# ShieldUart.net
KiCad netlist of a schematic drawn in Altium Designer
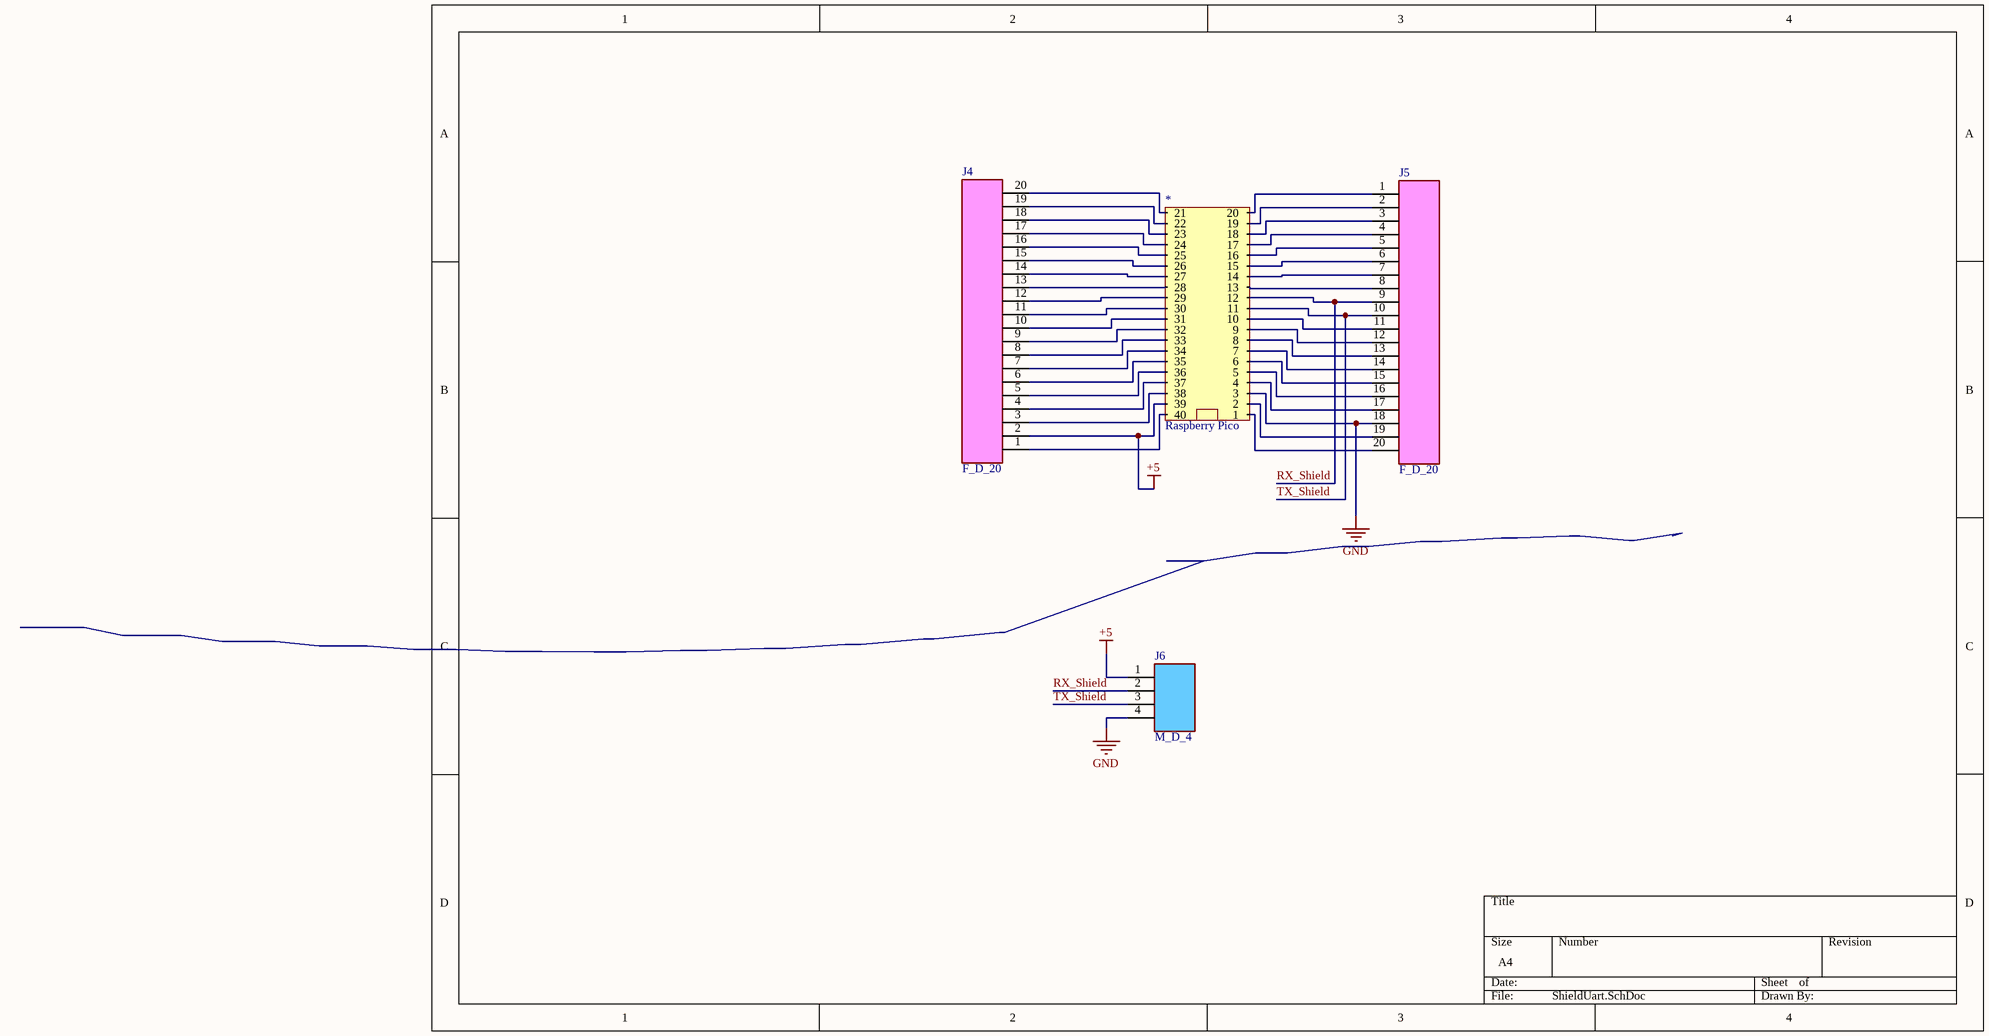
[diagram p0: ShieldUart.SchDoc]

(export (version "E")
  (design (tool "Eeschema 10.0.6"))
  (components
    (comp (ref "*")
      (value "Raspberry Pico")
      (footprint "Raspberry Pico")
      (libsource (lib "MyComponent") (part "Raspberry Pico"))
    )
    (comp (ref "J4")
      (value "BARRETTE_20 CONTACTS_1 RANGEE_FEMELLE_DROITE")
      (footprint "BARRETTE_20_F_D")
      (fields (field (name "TYPE") "F_D_20"))
      (libsource (lib "connecteurs") (part "BARRETTE_20 CONTACTS_1 RANGEE_FEMELLE_DROITE"))
    )
    (comp (ref "J5")
      (value "BARRETTE_20 CONTACTS_1 RANGEE_FEMELLE_DROITE")
      (footprint "BARRETTE_20_F_D")
      (fields (field (name "TYPE") "F_D_20"))
      (libsource (lib "") (part "BARRETTE_20 CONTACTS_1 RANGEE_FEMELLE_DROITE_1"))
    )
    (comp (ref "J6")
      (value "BARRETTE_4 CONTACTS_1 RANGEE_MALE_DROITE")
      (footprint "BARRETTE_4_M_D")
      (description "BARRETTE 4 CONTACTS 1 RANGEE MALE DROITE")
      (fields (field (name "TYPE") "M_D_4"))
      (libsource (lib "connecteurs") (part "BARRETTE_4 CONTACTS_1 RANGEE_MALE_DROITE"))
    )
  )
  (nets
    (net (code "1") (name "+5") (class "Default")
      (node (ref "*") (pin "39") (pinfunction "39_39") (pintype "passive"))
      (node (ref "J4") (pin "2") (pinfunction "2_2") (pintype "passive"))
      (node (ref "J6") (pin "1") (pinfunction "1_1") (pintype "passive"))
    )
    (net (code "2") (name "/RX_Shield") (class "Default")
      (node (ref "*") (pin "12") (pinfunction "12_12") (pintype "passive"))
      (node (ref "J5") (pin "9") (pinfunction "9_9") (pintype "passive"))
      (node (ref "J6") (pin "2") (pinfunction "2_2") (pintype "passive"))
    )
    (net (code "3") (name "/TX_Shield") (class "Default")
      (node (ref "*") (pin "11") (pinfunction "11_11") (pintype "passive"))
      (node (ref "J5") (pin "10") (pinfunction "10_10") (pintype "passive"))
      (node (ref "J6") (pin "3") (pinfunction "3_3") (pintype "passive"))
    )
    (net (code "4") (name "GND") (class "Default")
      (node (ref "*") (pin "3") (pinfunction "3_3") (pintype "passive"))
      (node (ref "J5") (pin "18") (pinfunction "18_18") (pintype "passive"))
      (node (ref "J6") (pin "4") (pinfunction "4_4") (pintype "passive"))
    )
    (net (code "5") (name "Net-(*-Pad1)") (class "Default")
      (node (ref "*") (pin "1") (pinfunction "1_1") (pintype "passive"))
      (node (ref "J5") (pin "20") (pinfunction "20_20") (pintype "passive"))
    )
    (net (code "6") (name "Net-(*-Pad2)") (class "Default")
      (node (ref "*") (pin "2") (pinfunction "2_2") (pintype "passive"))
      (node (ref "J5") (pin "19") (pinfunction "19_19") (pintype "passive"))
    )
    (net (code "7") (name "Net-(*-Pad4)") (class "Default")
      (node (ref "*") (pin "4") (pinfunction "4_4") (pintype "passive"))
      (node (ref "J5") (pin "17") (pinfunction "17_17") (pintype "passive"))
    )
    (net (code "8") (name "Net-(*-Pad5)") (class "Default")
      (node (ref "*") (pin "5") (pinfunction "5_5") (pintype "passive"))
      (node (ref "J5") (pin "16") (pinfunction "16_16") (pintype "passive"))
    )
    (net (code "9") (name "Net-(*-Pad6)") (class "Default")
      (node (ref "*") (pin "6") (pinfunction "6_6") (pintype "passive"))
      (node (ref "J5") (pin "15") (pinfunction "15_15") (pintype "passive"))
    )
    (net (code "10") (name "Net-(*-Pad7)") (class "Default")
      (node (ref "*") (pin "7") (pinfunction "7_7") (pintype "passive"))
      (node (ref "J5") (pin "14") (pinfunction "14_14") (pintype "passive"))
    )
    (net (code "11") (name "Net-(*-Pad8)") (class "Default")
      (node (ref "*") (pin "8") (pinfunction "8_8") (pintype "passive"))
      (node (ref "J5") (pin "13") (pinfunction "13_13") (pintype "passive"))
    )
    (net (code "12") (name "Net-(*-Pad9)") (class "Default")
      (node (ref "*") (pin "9") (pinfunction "9_9") (pintype "passive"))
      (node (ref "J5") (pin "12") (pinfunction "12_12") (pintype "passive"))
    )
    (net (code "13") (name "Net-(*-Pad10)") (class "Default")
      (node (ref "*") (pin "10") (pinfunction "10_10") (pintype "passive"))
      (node (ref "J5") (pin "11") (pinfunction "11_11") (pintype "passive"))
    )
    (net (code "14") (name "Net-(*-Pad13)") (class "Default")
      (node (ref "*") (pin "13") (pinfunction "13_13") (pintype "passive"))
      (node (ref "J5") (pin "8") (pinfunction "8_8") (pintype "passive"))
    )
    (net (code "15") (name "Net-(*-Pad14)") (class "Default")
      (node (ref "*") (pin "14") (pinfunction "14_14") (pintype "passive"))
      (node (ref "J5") (pin "7") (pinfunction "7_7") (pintype "passive"))
    )
    (net (code "16") (name "Net-(*-Pad15)") (class "Default")
      (node (ref "*") (pin "15") (pinfunction "15_15") (pintype "passive"))
      (node (ref "J5") (pin "6") (pinfunction "6_6") (pintype "passive"))
    )
    (net (code "17") (name "Net-(*-Pad16)") (class "Default")
      (node (ref "*") (pin "16") (pinfunction "16_16") (pintype "passive"))
      (node (ref "J5") (pin "5") (pinfunction "5_5") (pintype "passive"))
    )
    (net (code "18") (name "Net-(*-Pad17)") (class "Default")
      (node (ref "*") (pin "17") (pinfunction "17_17") (pintype "passive"))
      (node (ref "J5") (pin "4") (pinfunction "4_4") (pintype "passive"))
    )
    (net (code "19") (name "Net-(*-Pad18)") (class "Default")
      (node (ref "*") (pin "18") (pinfunction "18_18") (pintype "passive"))
      (node (ref "J5") (pin "3") (pinfunction "3_3") (pintype "passive"))
    )
    (net (code "20") (name "Net-(*-Pad19)") (class "Default")
      (node (ref "*") (pin "19") (pinfunction "19_19") (pintype "passive"))
      (node (ref "J5") (pin "2") (pinfunction "2_2") (pintype "passive"))
    )
    (net (code "21") (name "Net-(*-Pad20)") (class "Default")
      (node (ref "*") (pin "20") (pinfunction "20_20") (pintype "passive"))
      (node (ref "J5") (pin "1") (pinfunction "1_1") (pintype "passive"))
    )
    (net (code "22") (name "Net-(*-Pad21)") (class "Default")
      (node (ref "*") (pin "21") (pinfunction "21_21") (pintype "passive"))
      (node (ref "J4") (pin "20") (pinfunction "20_20") (pintype "passive"))
    )
    (net (code "23") (name "Net-(*-Pad22)") (class "Default")
      (node (ref "*") (pin "22") (pinfunction "22_22") (pintype "passive"))
      (node (ref "J4") (pin "19") (pinfunction "19_19") (pintype "passive"))
    )
    (net (code "24") (name "Net-(*-Pad23)") (class "Default")
      (node (ref "*") (pin "23") (pinfunction "23_23") (pintype "passive"))
      (node (ref "J4") (pin "18") (pinfunction "18_18") (pintype "passive"))
    )
    (net (code "25") (name "Net-(*-Pad24)") (class "Default")
      (node (ref "*") (pin "24") (pinfunction "24_24") (pintype "passive"))
      (node (ref "J4") (pin "17") (pinfunction "17_17") (pintype "passive"))
    )
    (net (code "26") (name "Net-(*-Pad25)") (class "Default")
      (node (ref "*") (pin "25") (pinfunction "25_25") (pintype "passive"))
      (node (ref "J4") (pin "16") (pinfunction "16_16") (pintype "passive"))
    )
    (net (code "27") (name "Net-(*-Pad26)") (class "Default")
      (node (ref "*") (pin "26") (pinfunction "26_26") (pintype "passive"))
      (node (ref "J4") (pin "15") (pinfunction "15_15") (pintype "passive"))
    )
    (net (code "28") (name "Net-(*-Pad27)") (class "Default")
      (node (ref "*") (pin "27") (pinfunction "27_27") (pintype "passive"))
      (node (ref "J4") (pin "14") (pinfunction "14_14") (pintype "passive"))
    )
    (net (code "29") (name "Net-(*-Pad28)") (class "Default")
      (node (ref "*") (pin "28") (pinfunction "28_28") (pintype "passive"))
      (node (ref "J4") (pin "13") (pinfunction "13_13") (pintype "passive"))
    )
    (net (code "30") (name "Net-(*-Pad29)") (class "Default")
      (node (ref "*") (pin "29") (pinfunction "29_29") (pintype "passive"))
      (node (ref "J4") (pin "12") (pinfunction "12_12") (pintype "passive"))
    )
    (net (code "31") (name "Net-(*-Pad30)") (class "Default")
      (node (ref "*") (pin "30") (pinfunction "30_30") (pintype "passive"))
      (node (ref "J4") (pin "11") (pinfunction "11_11") (pintype "passive"))
    )
    (net (code "32") (name "Net-(*-Pad31)") (class "Default")
      (node (ref "*") (pin "31") (pinfunction "31_31") (pintype "passive"))
      (node (ref "J4") (pin "10") (pinfunction "10_10") (pintype "passive"))
    )
    (net (code "33") (name "Net-(*-Pad32)") (class "Default")
      (node (ref "*") (pin "32") (pinfunction "32_32") (pintype "passive"))
      (node (ref "J4") (pin "9") (pinfunction "9_9") (pintype "passive"))
    )
    (net (code "34") (name "Net-(*-Pad33)") (class "Default")
      (node (ref "*") (pin "33") (pinfunction "33_33") (pintype "passive"))
      (node (ref "J4") (pin "8") (pinfunction "8_8") (pintype "passive"))
    )
    (net (code "35") (name "Net-(*-Pad34)") (class "Default")
      (node (ref "*") (pin "34") (pinfunction "34_34") (pintype "passive"))
      (node (ref "J4") (pin "7") (pinfunction "7_7") (pintype "passive"))
    )
    (net (code "36") (name "Net-(*-Pad35)") (class "Default")
      (node (ref "*") (pin "35") (pinfunction "35_35") (pintype "passive"))
      (node (ref "J4") (pin "6") (pinfunction "6_6") (pintype "passive"))
    )
    (net (code "37") (name "Net-(*-Pad36)") (class "Default")
      (node (ref "*") (pin "36") (pinfunction "36_36") (pintype "passive"))
      (node (ref "J4") (pin "5") (pinfunction "5_5") (pintype "passive"))
    )
    (net (code "38") (name "Net-(*-Pad37)") (class "Default")
      (node (ref "*") (pin "37") (pinfunction "37_37") (pintype "passive"))
      (node (ref "J4") (pin "4") (pinfunction "4_4") (pintype "passive"))
    )
    (net (code "39") (name "Net-(*-Pad38)") (class "Default")
      (node (ref "*") (pin "38") (pinfunction "38_38") (pintype "passive"))
      (node (ref "J4") (pin "3") (pinfunction "3_3") (pintype "passive"))
    )
    (net (code "40") (name "Net-(*-Pad40)") (class "Default")
      (node (ref "*") (pin "40") (pinfunction "40_40") (pintype "passive"))
      (node (ref "J4") (pin "1") (pinfunction "1_1") (pintype "passive"))
    )
  )
)
